# cyberstick3_rec.net
KiCad netlist of a schematic drawn in EAGLE
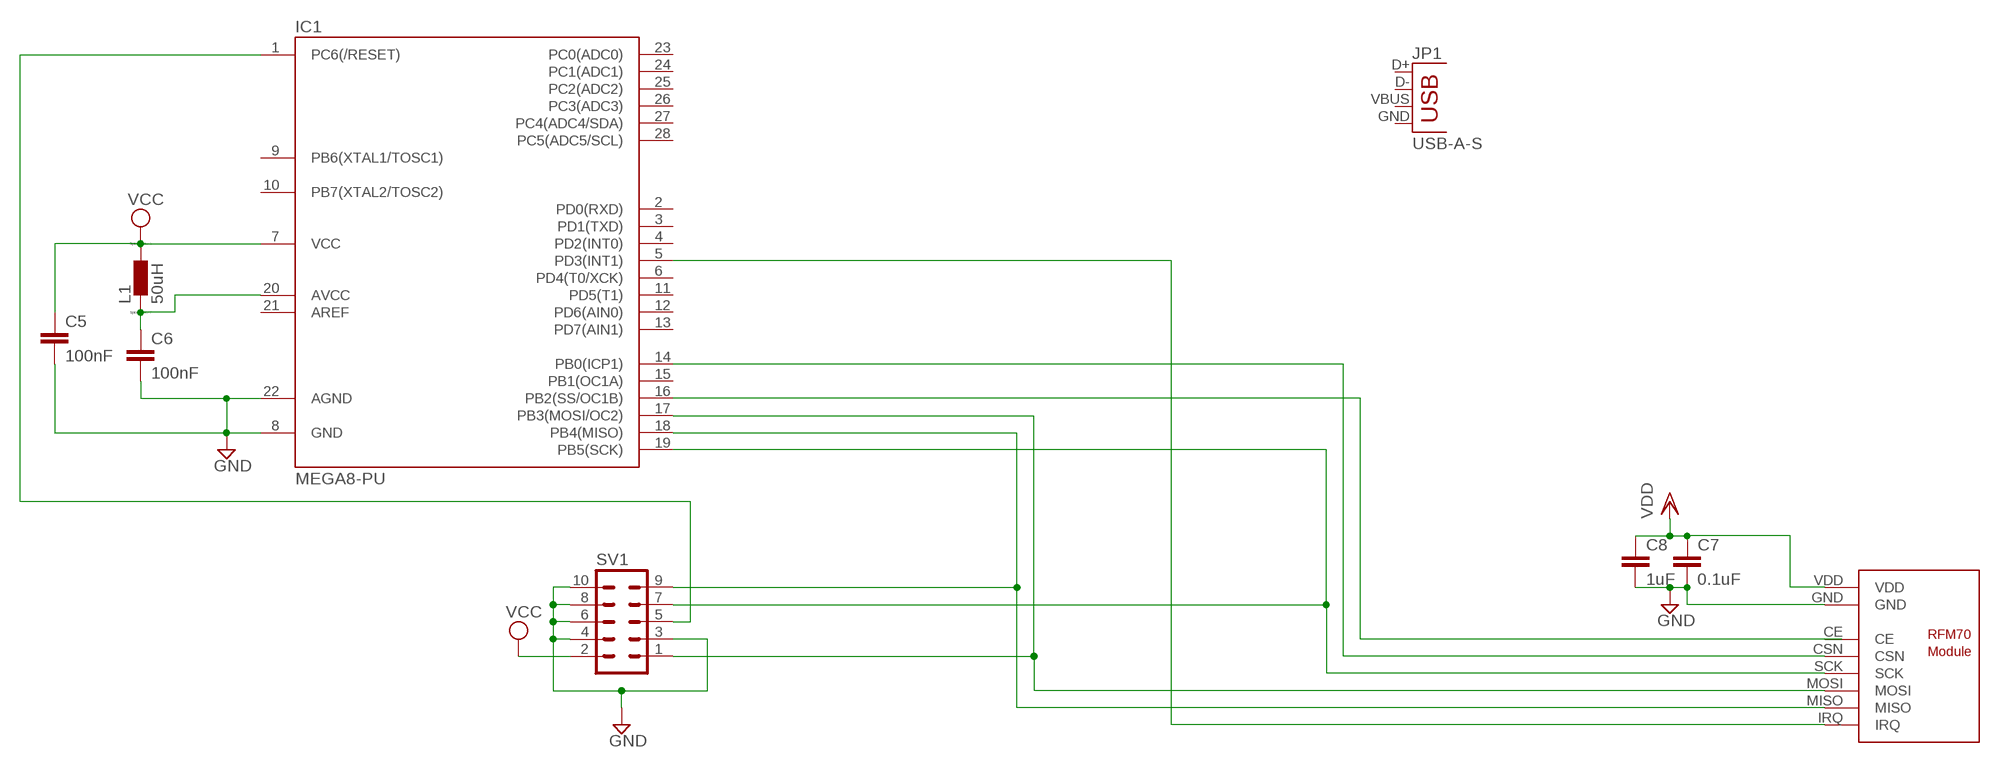
[diagram p0: schematic, sheet 1]

(export (version "E")
  (design (tool "Eeschema 10.0.6"))
  (components
    (comp (ref "C5")
      (value "100nF")
      (footprint "eagle-import:C2.5-3")
      (libsource (lib "eagle-import") (part "C2,5-3"))
    )
    (comp (ref "C6")
      (value "100nF")
      (footprint "eagle-import:C2.5-3")
      (libsource (lib "eagle-import") (part "C2,5-3"))
    )
    (comp (ref "C7")
      (value "0.1uF")
      (footprint "eagle-import:C2.5-3")
      (libsource (lib "eagle-import") (part "C2,5-3"))
    )
    (comp (ref "C8")
      (value "1uF")
      (footprint "eagle-import:C2.5-3")
      (libsource (lib "eagle-import") (part "C2,5-3"))
    )
    (comp (ref "IC1")
      (value "MEGA8-PU")
      (footprint "eagle-import:DIL28-3")
      (libsource (lib "eagle-import") (part "MEGA8-PU"))
    )
    (comp (ref "JP1")
      (value "USB-A-S")
      (footprint "eagle-import:USB-A-S")
      (libsource (lib "eagle-import") (part "USB-A-S"))
    )
    (comp (ref "L1")
      (value "50uH")
      (footprint "eagle-import:0204_7")
      (libsource (lib "eagle-import") (part "L0204/7"))
    )
    (comp (ref "SV1")
      (value "MA05-2")
      (footprint "eagle-import:MA05-2")
      (libsource (lib "eagle-import") (part "MA05-2"))
    )
    (comp (ref "U$2")
      (value "RFM70")
      (footprint "eagle-import:RFM70")
      (libsource (lib "eagle-import") (part "RFM70"))
    )
  )
  (nets
    (net (code "1") (name "GND") (class "Default")
      (node (ref "C5") (pin "2") (pinfunction "2_2") (pintype "passive"))
      (node (ref "C6") (pin "2") (pinfunction "2_2") (pintype "passive"))
      (node (ref "C7") (pin "2") (pinfunction "2_2") (pintype "passive"))
      (node (ref "C8") (pin "2") (pinfunction "2_2") (pintype "passive"))
      (node (ref "IC1") (pin "22") (pinfunction "AGND_22") (pintype "power_in"))
      (node (ref "IC1") (pin "8") (pinfunction "GND_8") (pintype "power_in"))
      (node (ref "SV1") (pin "10") (pinfunction "10_10") (pintype "passive"))
      (node (ref "SV1") (pin "3") (pinfunction "3_3") (pintype "passive"))
      (node (ref "SV1") (pin "4") (pinfunction "4_4") (pintype "passive"))
      (node (ref "SV1") (pin "6") (pinfunction "6_6") (pintype "passive"))
      (node (ref "SV1") (pin "8") (pinfunction "8_8") (pintype "passive"))
      (node (ref "U$2") (pin "GND") (pinfunction "GND_GND") (pintype "power_in"))
    )
    (net (code "2") (name "Net-(IC1-AVCC)") (class "Default")
      (node (ref "C6") (pin "1") (pinfunction "1_1") (pintype "passive"))
      (node (ref "IC1") (pin "20") (pinfunction "AVCC_20") (pintype "passive"))
      (node (ref "L1") (pin "2") (pinfunction "2_2") (pintype "passive"))
    )
    (net (code "3") (name "Net-(IC1-PB0(ICP1))") (class "Default")
      (node (ref "IC1") (pin "14") (pinfunction "PB0(ICP1)_14") (pintype "bidirectional"))
      (node (ref "U$2") (pin "CSN") (pinfunction "CSN_CSN") (pintype "bidirectional"))
    )
    (net (code "4") (name "Net-(IC1-PB3(MOSI{slash}OC2))") (class "Default")
      (node (ref "IC1") (pin "17") (pinfunction "PB3(MOSI/OC2)_17") (pintype "bidirectional"))
      (node (ref "SV1") (pin "1") (pinfunction "1_1") (pintype "passive"))
      (node (ref "U$2") (pin "MOSI") (pinfunction "MOSI_MOSI") (pintype "bidirectional"))
    )
    (net (code "5") (name "Net-(IC1-PB4(MISO))") (class "Default")
      (node (ref "IC1") (pin "18") (pinfunction "PB4(MISO)_18") (pintype "bidirectional"))
      (node (ref "SV1") (pin "9") (pinfunction "9_9") (pintype "passive"))
      (node (ref "U$2") (pin "MISO") (pinfunction "MISO_MISO") (pintype "bidirectional"))
    )
    (net (code "6") (name "Net-(IC1-PB5(SCK))") (class "Default")
      (node (ref "IC1") (pin "19") (pinfunction "PB5(SCK)_19") (pintype "bidirectional"))
      (node (ref "SV1") (pin "7") (pinfunction "7_7") (pintype "passive"))
      (node (ref "U$2") (pin "SCK") (pinfunction "SCK_SCK") (pintype "bidirectional"))
    )
    (net (code "7") (name "Net-(IC1-PC6({slash}RESET))") (class "Default")
      (node (ref "IC1") (pin "1") (pinfunction "PC6(/RESET)_1") (pintype "bidirectional"))
      (node (ref "SV1") (pin "5") (pinfunction "5_5") (pintype "passive"))
    )
    (net (code "8") (name "Net-(IC1-PD3(INT1))") (class "Default")
      (node (ref "IC1") (pin "5") (pinfunction "PD3(INT1)_5") (pintype "bidirectional"))
      (node (ref "U$2") (pin "IRQ") (pinfunction "IRQ_IRQ") (pintype "bidirectional"))
    )
    (net (code "9") (name "VCC") (class "Default")
      (node (ref "C5") (pin "1") (pinfunction "1_1") (pintype "passive"))
      (node (ref "IC1") (pin "7") (pinfunction "VCC_7") (pintype "power_in"))
      (node (ref "L1") (pin "1") (pinfunction "1_1") (pintype "passive"))
      (node (ref "SV1") (pin "2") (pinfunction "2_2") (pintype "passive"))
    )
    (net (code "10") (name "VDD") (class "Default")
      (node (ref "C7") (pin "1") (pinfunction "1_1") (pintype "passive"))
      (node (ref "C8") (pin "1") (pinfunction "1_1") (pintype "passive"))
      (node (ref "U$2") (pin "VDD") (pinfunction "VDD_VDD") (pintype "power_in"))
    )
    (net (code "11") (name "unconnected-(IC1-AREF-Pad21)") (class "Default")
      (node (ref "IC1") (pin "21") (pinfunction "AREF_21") (pintype "passive"))
    )
    (net (code "12") (name "unconnected-(IC1-PB1(OC1A)-Pad15)") (class "Default")
      (node (ref "IC1") (pin "15") (pinfunction "PB1(OC1A)_15") (pintype "bidirectional"))
    )
    (net (code "13") (name "unconnected-(IC1-PB2(SS{slash}OC1B)-Pad16)") (class "Default")
      (node (ref "IC1") (pin "16") (pinfunction "PB2(SS/OC1B)_16") (pintype "bidirectional"))
    )
    (net (code "14") (name "unconnected-(IC1-PB6(XTAL1{slash}TOSC1)-Pad9)") (class "Default")
      (node (ref "IC1") (pin "9") (pinfunction "PB6(XTAL1/TOSC1)_9") (pintype "bidirectional"))
    )
    (net (code "15") (name "unconnected-(IC1-PB7(XTAL2{slash}TOSC2)-Pad10)") (class "Default")
      (node (ref "IC1") (pin "10") (pinfunction "PB7(XTAL2/TOSC2)_10") (pintype "bidirectional"))
    )
    (net (code "16") (name "unconnected-(IC1-PC0(ADC0)-Pad23)") (class "Default")
      (node (ref "IC1") (pin "23") (pinfunction "PC0(ADC0)_23") (pintype "bidirectional"))
    )
    (net (code "17") (name "unconnected-(IC1-PC1(ADC1)-Pad24)") (class "Default")
      (node (ref "IC1") (pin "24") (pinfunction "PC1(ADC1)_24") (pintype "bidirectional"))
    )
    (net (code "18") (name "unconnected-(IC1-PC2(ADC2)-Pad25)") (class "Default")
      (node (ref "IC1") (pin "25") (pinfunction "PC2(ADC2)_25") (pintype "bidirectional"))
    )
    (net (code "19") (name "unconnected-(IC1-PC3(ADC3)-Pad26)") (class "Default")
      (node (ref "IC1") (pin "26") (pinfunction "PC3(ADC3)_26") (pintype "bidirectional"))
    )
    (net (code "20") (name "unconnected-(IC1-PC4(ADC4{slash}SDA)-Pad27)") (class "Default")
      (node (ref "IC1") (pin "27") (pinfunction "PC4(ADC4/SDA)_27") (pintype "bidirectional"))
    )
    (net (code "21") (name "unconnected-(IC1-PC5(ADC5{slash}SCL)-Pad28)") (class "Default")
      (node (ref "IC1") (pin "28") (pinfunction "PC5(ADC5/SCL)_28") (pintype "bidirectional"))
    )
    (net (code "22") (name "unconnected-(IC1-PD0(RXD)-Pad2)") (class "Default")
      (node (ref "IC1") (pin "2") (pinfunction "PD0(RXD)_2") (pintype "bidirectional"))
    )
    (net (code "23") (name "unconnected-(IC1-PD1(TXD)-Pad3)") (class "Default")
      (node (ref "IC1") (pin "3") (pinfunction "PD1(TXD)_3") (pintype "bidirectional"))
    )
    (net (code "24") (name "unconnected-(IC1-PD2(INT0)-Pad4)") (class "Default")
      (node (ref "IC1") (pin "4") (pinfunction "PD2(INT0)_4") (pintype "bidirectional"))
    )
    (net (code "25") (name "unconnected-(IC1-PD4(T0{slash}XCK)-Pad6)") (class "Default")
      (node (ref "IC1") (pin "6") (pinfunction "PD4(T0/XCK)_6") (pintype "bidirectional"))
    )
    (net (code "26") (name "unconnected-(IC1-PD5(T1)-Pad11)") (class "Default")
      (node (ref "IC1") (pin "11") (pinfunction "PD5(T1)_11") (pintype "bidirectional"))
    )
    (net (code "27") (name "unconnected-(IC1-PD6(AIN0)-Pad12)") (class "Default")
      (node (ref "IC1") (pin "12") (pinfunction "PD6(AIN0)_12") (pintype "bidirectional"))
    )
    (net (code "28") (name "unconnected-(IC1-PD7(AIN1)-Pad13)") (class "Default")
      (node (ref "IC1") (pin "13") (pinfunction "PD7(AIN1)_13") (pintype "bidirectional"))
    )
    (net (code "29") (name "unconnected-(JP1-PadD+)") (class "Default")
      (node (ref "JP1") (pin "D+") (pinfunction "D+_D+") (pintype "bidirectional"))
    )
    (net (code "30") (name "unconnected-(JP1-PadD-)") (class "Default")
      (node (ref "JP1") (pin "D-") (pinfunction "D-_D-") (pintype "bidirectional"))
    )
    (net (code "31") (name "unconnected-(JP1-PadGND)") (class "Default")
      (node (ref "JP1") (pin "GND") (pinfunction "GND_GND") (pintype "bidirectional"))
    )
    (net (code "32") (name "unconnected-(JP1-PadVBUS)") (class "Default")
      (node (ref "JP1") (pin "VBUS") (pinfunction "VBUS_VBUS") (pintype "bidirectional"))
    )
    (net (code "33") (name "unconnected-(U$2-PadCE)") (class "Default")
      (node (ref "U$2") (pin "CE") (pinfunction "CE_CE") (pintype "bidirectional"))
    )
  )
)
